# HighPassFilter.net
KiCad netlist of a schematic drawn in Altium Designer
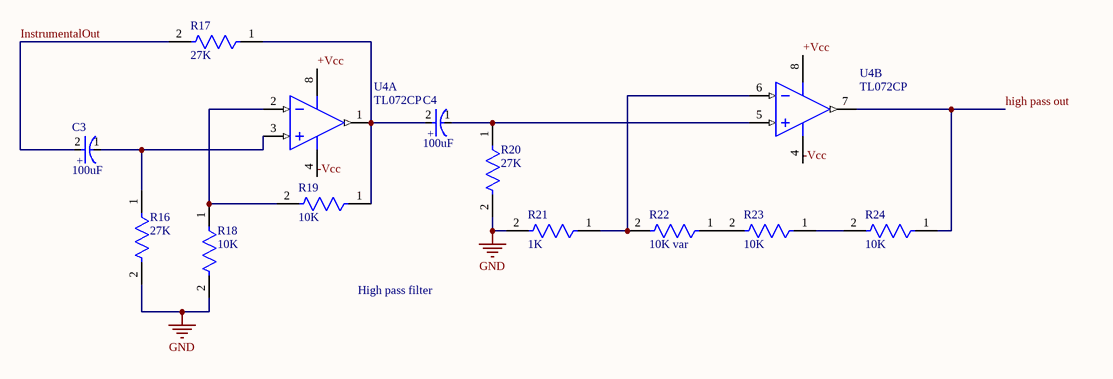
[diagram p0: HighPassFilter.SchDoc]

(export (version "E")
  (design (tool "Eeschema 10.0.6"))
  (components
    (comp (ref "C3")
      (value "100uF")
      (footprint "FP-RAD-TH-D_6_3_0_5-L_11-MFG")
      (description "Aluminum Electrolytic Capacitors (Radial Lead Type) 4.7uF ±20% 160V")
      (fields (field (name "VOLTAGE") "160V") (field (name "TOLERANCE") "20%"))
      (libsource (lib "Altium Content Vault") (part "203bc49f2ac43e59fd269a8c329ed05"))
    )
    (comp (ref "C4")
      (value "100uF")
      (footprint "FP-RAD-TH-D_6_3_0_5-L_11-MFG")
      (description "Aluminum Electrolytic Capacitors (Radial Lead Type) 4.7uF ±20% 160V")
      (fields (field (name "VOLTAGE") "160V") (field (name "TOLERANCE") "20%"))
      (libsource (lib "Altium Content Vault") (part "203bc49f2ac43e59fd269a8c329ed05"))
    )
    (comp (ref "R16")
      (value "27K")
      (footprint "FP-CFR-25-MFG")
      (description "RES 10 OHM 1/4W 5% AXIAL")
      (fields (field (name "TOLERANCE") "5%"))
      (libsource (lib "Altium Content Vault") (part "1029c3af85768c4190bb7ad29bc67b5"))
    )
    (comp (ref "R17")
      (value "27K")
      (footprint "FP-CFR-25-MFG")
      (description "RES 10 OHM 1/4W 5% AXIAL")
      (fields (field (name "TOLERANCE") "5%"))
      (libsource (lib "Altium Content Vault") (part "1029c3af85768c4190bb7ad29bc67b5"))
    )
    (comp (ref "R18")
      (value "10K")
      (footprint "FP-CFR-25-MFG")
      (description "RES 10 OHM 1/4W 5% AXIAL")
      (fields (field (name "TOLERANCE") "5%"))
      (libsource (lib "Altium Content Vault") (part "1029c3af85768c4190bb7ad29bc67b5"))
    )
    (comp (ref "R19")
      (value "10K")
      (footprint "FP-CFR-25-MFG")
      (description "RES 10 OHM 1/4W 5% AXIAL")
      (fields (field (name "TOLERANCE") "5%"))
      (libsource (lib "Altium Content Vault") (part "1029c3af85768c4190bb7ad29bc67b5"))
    )
    (comp (ref "R20")
      (value "27K")
      (footprint "FP-CFR-25-MFG")
      (description "RES 10 OHM 1/4W 5% AXIAL")
      (fields (field (name "TOLERANCE") "5%"))
      (libsource (lib "Altium Content Vault") (part "1029c3af85768c4190bb7ad29bc67b5"))
    )
    (comp (ref "R21")
      (value "1K")
      (footprint "FP-CFR-25-MFG")
      (description "RES 10 OHM 1/4W 5% AXIAL")
      (fields (field (name "TOLERANCE") "5%"))
      (libsource (lib "Altium Content Vault") (part "1029c3af85768c4190bb7ad29bc67b5"))
    )
    (comp (ref "R22")
      (value "10K var")
      (footprint "FP-CFR-25-MFG")
      (description "RES 10 OHM 1/4W 5% AXIAL")
      (fields (field (name "TOLERANCE") "5%"))
      (libsource (lib "Altium Content Vault") (part "1029c3af85768c4190bb7ad29bc67b5"))
    )
    (comp (ref "R23")
      (value "10K")
      (footprint "FP-CFR-25-MFG")
      (description "RES 10 OHM 1/4W 5% AXIAL")
      (fields (field (name "TOLERANCE") "5%"))
      (libsource (lib "Altium Content Vault") (part "1029c3af85768c4190bb7ad29bc67b5"))
    )
    (comp (ref "R24")
      (value "10K")
      (footprint "FP-CFR-25-MFG")
      (description "RES 10 OHM 1/4W 5% AXIAL")
      (fields (field (name "TOLERANCE") "5%"))
      (libsource (lib "Altium Content Vault") (part "1029c3af85768c4190bb7ad29bc67b5"))
    )
    (comp (ref "U4")
      (value "TL072CP")
      (footprint "P0008A")
      (fields (field (name "MANUFACTURER") "Texas Instruments"))
      (libsource (lib "Altium Content Vault") (part "TI-AMP-D6-2-8_D"))
    )
  )
  (nets
    (net (code "1") (name "/+Vcc") (class "Default")
      (node (ref "U4") (pin "8") (pinfunction "VCC+_8") (pintype "power_in"))
    )
    (net (code "2") (name "/-Vcc") (class "Default")
      (node (ref "U4") (pin "4") (pinfunction "VCC-_4") (pintype "power_in"))
    )
    (net (code "3") (name "/InstrumentalOut") (class "Default")
      (node (ref "C3") (pin "2") (pinfunction "A_2") (pintype "passive"))
      (node (ref "R17") (pin "2") (pinfunction "2_2") (pintype "passive"))
    )
    (net (code "4") (name "/high pass out") (class "Default")
      (node (ref "R24") (pin "1") (pinfunction "1_1") (pintype "passive"))
      (node (ref "U4") (pin "7") (pinfunction "OUT2_7") (pintype "output"))
    )
    (net (code "5") (name "GND") (class "Default")
      (node (ref "R16") (pin "2") (pinfunction "2_2") (pintype "passive"))
      (node (ref "R18") (pin "2") (pinfunction "2_2") (pintype "passive"))
      (node (ref "R20") (pin "2") (pinfunction "2_2") (pintype "passive"))
      (node (ref "R21") (pin "2") (pinfunction "2_2") (pintype "passive"))
    )
    (net (code "6") (name "Net-(C3-C)") (class "Default")
      (node (ref "C3") (pin "1") (pinfunction "C_1") (pintype "passive"))
      (node (ref "R16") (pin "1") (pinfunction "1_1") (pintype "passive"))
      (node (ref "U4") (pin "3") (pinfunction "IN1+_3") (pintype "input"))
    )
    (net (code "7") (name "Net-(C4-A)") (class "Default")
      (node (ref "C4") (pin "2") (pinfunction "A_2") (pintype "passive"))
      (node (ref "R17") (pin "1") (pinfunction "1_1") (pintype "passive"))
      (node (ref "R19") (pin "1") (pinfunction "1_1") (pintype "passive"))
      (node (ref "U4") (pin "1") (pinfunction "OUT1_1") (pintype "output"))
    )
    (net (code "8") (name "Net-(C4-C)") (class "Default")
      (node (ref "C4") (pin "1") (pinfunction "C_1") (pintype "passive"))
      (node (ref "R20") (pin "1") (pinfunction "1_1") (pintype "passive"))
      (node (ref "U4") (pin "5") (pinfunction "IN2+_5") (pintype "input"))
    )
    (net (code "9") (name "Net-(R22-Pad1)") (class "Default")
      (node (ref "R22") (pin "1") (pinfunction "1_1") (pintype "passive"))
      (node (ref "R23") (pin "2") (pinfunction "2_2") (pintype "passive"))
    )
    (net (code "10") (name "Net-(R23-Pad1)") (class "Default")
      (node (ref "R23") (pin "1") (pinfunction "1_1") (pintype "passive"))
      (node (ref "R24") (pin "2") (pinfunction "2_2") (pintype "passive"))
    )
    (net (code "11") (name "Net-(U4A-IN1-)") (class "Default")
      (node (ref "R18") (pin "1") (pinfunction "1_1") (pintype "passive"))
      (node (ref "R19") (pin "2") (pinfunction "2_2") (pintype "passive"))
      (node (ref "U4") (pin "2") (pinfunction "IN1-_2") (pintype "input"))
    )
    (net (code "12") (name "Net-(U4B-IN2-)") (class "Default")
      (node (ref "R21") (pin "1") (pinfunction "1_1") (pintype "passive"))
      (node (ref "R22") (pin "2") (pinfunction "2_2") (pintype "passive"))
      (node (ref "U4") (pin "6") (pinfunction "IN2-_6") (pintype "input"))
    )
  )
)
